# APDS-9200.net
KiCad netlist of a schematic drawn in EAGLE
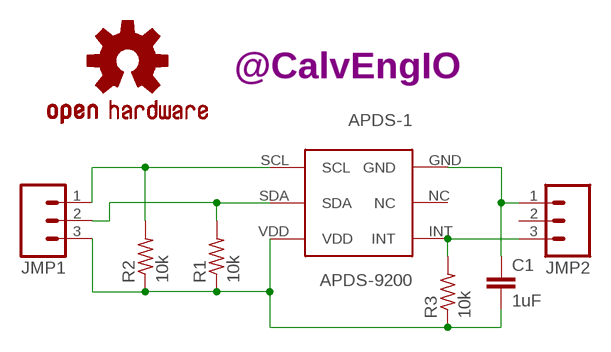
[diagram p0: schematic, sheet 1]

(export (version "E")
  (design (tool "Eeschema 10.0.6"))
  (components
    (comp (ref "APDS-1")
      (value "APDS-9200")
      (footprint "eagle-import:APDS-9200")
      (libsource (lib "eagle-import") (part "APDS-9200"))
    )
    (comp (ref "C1")
      (value "1uF")
      (footprint "eagle-import:C0402")
      (libsource (lib "eagle-import") (part "CAPACITOR0402"))
    )
    (comp (ref "JMP1")
      (value "JMP-03")
      (footprint "eagle-import:1X03@1")
      (libsource (lib "eagle-import") (part "JMP-03"))
    )
    (comp (ref "JMP2")
      (value "JMP-03")
      (footprint "eagle-import:1X03@1")
      (libsource (lib "eagle-import") (part "JMP-03"))
    )
    (comp (ref "LOGO1")
      (value "OSHW-LOGOMINI")
      (footprint "eagle-import:OSHW-LOGO-MINI")
      (libsource (lib "eagle-import") (part "OSHW-LOGOMINI"))
    )
    (comp (ref "R1")
      (value "10k")
      (footprint "eagle-import:R0402")
      (libsource (lib "eagle-import") (part "RESISTOR0402"))
    )
    (comp (ref "R2")
      (value "10k")
      (footprint "eagle-import:R0402")
      (libsource (lib "eagle-import") (part "RESISTOR0402"))
    )
    (comp (ref "R3")
      (value "10k")
      (footprint "eagle-import:R0402")
      (libsource (lib "eagle-import") (part "RESISTOR0402"))
    )
    (comp (ref "U$1")
      (value "CALVENGIO_HANDLEHANDLE.025")
      (footprint "eagle-import:CALVENGIO_HANDLE.025")
      (libsource (lib "eagle-import") (part "CALVENGIO_HANDLEHANDLE.025"))
    )
  )
  (nets
    (net (code "1") (name "Net-(JMP1-2)") (class "Default")
      (node (ref "APDS-1") (pin "SCL") (pinfunction "SCL_SCL") (pintype "bidirectional"))
      (node (ref "JMP1") (pin "1") (pinfunction "2_1") (pintype "passive"))
      (node (ref "R2") (pin "2") (pinfunction "2_2") (pintype "passive"))
    )
    (net (code "2") (name "Net-(JMP1-3)") (class "Default")
      (node (ref "APDS-1") (pin "SDA") (pinfunction "SDA_SDA") (pintype "bidirectional"))
      (node (ref "JMP1") (pin "2") (pinfunction "3_2") (pintype "passive"))
      (node (ref "R1") (pin "2") (pinfunction "2_2") (pintype "passive"))
    )
    (net (code "3") (name "Net-(JMP1-4)") (class "Default")
      (node (ref "APDS-1") (pin "VDD") (pinfunction "VDD_VDD") (pintype "bidirectional"))
      (node (ref "C1") (pin "2") (pinfunction "2_2") (pintype "passive"))
      (node (ref "JMP1") (pin "3") (pinfunction "4_3") (pintype "passive"))
      (node (ref "R1") (pin "1") (pinfunction "1_1") (pintype "passive"))
      (node (ref "R2") (pin "1") (pinfunction "1_1") (pintype "passive"))
      (node (ref "R3") (pin "1") (pinfunction "1_1") (pintype "passive"))
    )
    (net (code "4") (name "Net-(JMP2-2)") (class "Default")
      (node (ref "APDS-1") (pin "GND") (pinfunction "GND_GND") (pintype "bidirectional"))
      (node (ref "C1") (pin "1") (pinfunction "1_1") (pintype "passive"))
      (node (ref "JMP2") (pin "1") (pinfunction "2_1") (pintype "passive"))
    )
    (net (code "5") (name "Net-(JMP2-4)") (class "Default")
      (node (ref "APDS-1") (pin "INT") (pinfunction "INT_INT") (pintype "bidirectional"))
      (node (ref "JMP2") (pin "3") (pinfunction "4_3") (pintype "passive"))
      (node (ref "R3") (pin "2") (pinfunction "2_2") (pintype "passive"))
    )
    (net (code "6") (name "unconnected-(APDS-1-PadNC)") (class "Default")
      (node (ref "APDS-1") (pin "NC") (pinfunction "NC_NC") (pintype "bidirectional"))
    )
    (net (code "7") (name "unconnected-(JMP2-3-Pad2)") (class "Default")
      (node (ref "JMP2") (pin "2") (pinfunction "3_2") (pintype "passive"))
    )
  )
)
